# Main_PDSplitter.net
KiCad netlist of a schematic drawn in Altium Designer
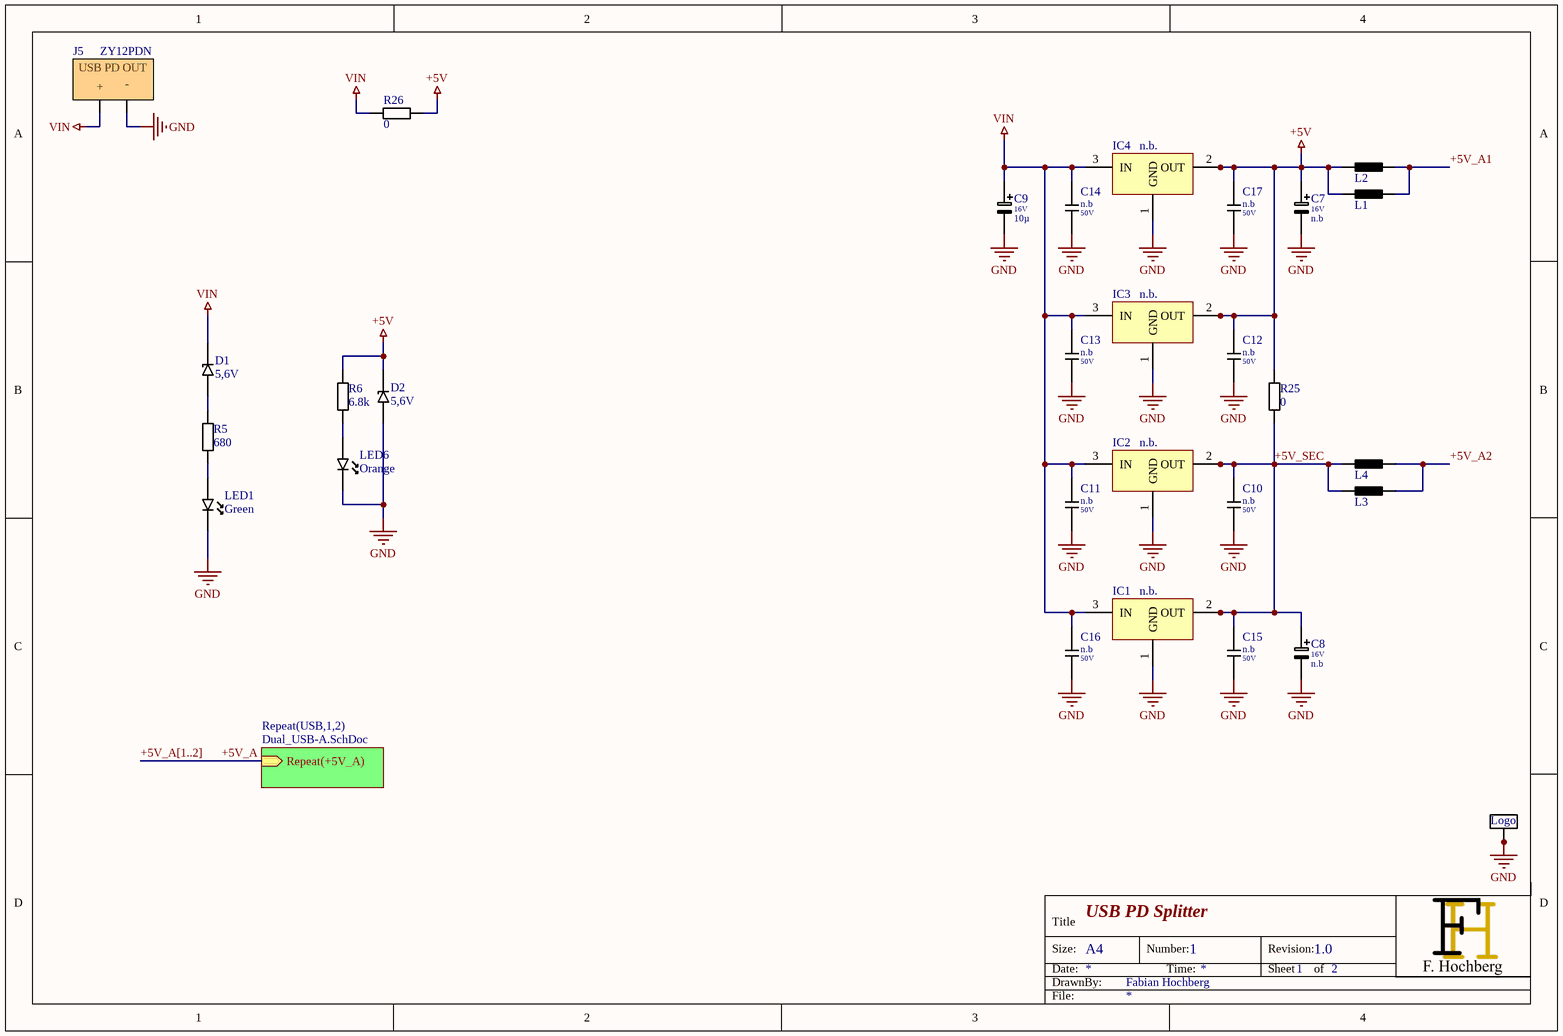
[diagram p0: Main_PDSplitter.SchDoc]

(export (version "E")
  (design (tool "Eeschema 10.0.6"))
  (components
    (comp (ref "C7")
      (value "n.b")
      (footprint "CAPAE_4x5.4")
      (description "Elko")
      (fields (field (name "VOLTAGE") "16V") (field (name "Comment") "n.b."))
      (libsource (lib "Passives_FH") (part "C POL"))
    )
    (comp (ref "C8")
      (value "n.b")
      (footprint "CAPAE_4x5.4")
      (description "Elko")
      (fields (field (name "VOLTAGE") "16V") (field (name "Comment") "n.b."))
      (libsource (lib "Passives_FH") (part "C POL"))
    )
    (comp (ref "C9")
      (value "10µ")
      (footprint "CAPAE_4x5.4")
      (description "Elko")
      (fields (field (name "VOLTAGE") "16V") (field (name "Comment") "10µ_16V"))
      (libsource (lib "Passives_FH") (part "C POL"))
    )
    (comp (ref "C10")
      (value "n.b")
      (footprint "0603_C")
      (description "Keramikkondensator")
      (fields (field (name "VOLTAGE") "50V") (field (name "Comment") "n.b."))
      (libsource (lib "Passives_FH") (part "C"))
    )
    (comp (ref "C11")
      (value "n.b")
      (footprint "0603_C")
      (description "Keramikkondensator")
      (fields (field (name "VOLTAGE") "50V") (field (name "Comment") "n.b."))
      (libsource (lib "Passives_FH") (part "C"))
    )
    (comp (ref "C12")
      (value "n.b")
      (footprint "0603_C")
      (description "Keramikkondensator")
      (fields (field (name "VOLTAGE") "50V") (field (name "Comment") "n.b."))
      (libsource (lib "Passives_FH") (part "C"))
    )
    (comp (ref "C13")
      (value "n.b")
      (footprint "0603_C")
      (description "Keramikkondensator")
      (fields (field (name "VOLTAGE") "50V") (field (name "Comment") "n.b."))
      (libsource (lib "Passives_FH") (part "C"))
    )
    (comp (ref "C14")
      (value "n.b")
      (footprint "0603_C")
      (description "Keramikkondensator")
      (fields (field (name "VOLTAGE") "50V") (field (name "Comment") "n.b."))
      (libsource (lib "Passives_FH") (part "C"))
    )
    (comp (ref "C15")
      (value "n.b")
      (footprint "0603_C")
      (description "Keramikkondensator")
      (fields (field (name "VOLTAGE") "50V") (field (name "Comment") "n.b."))
      (libsource (lib "Passives_FH") (part "C"))
    )
    (comp (ref "C16")
      (value "n.b")
      (footprint "0603_C")
      (description "Keramikkondensator")
      (fields (field (name "VOLTAGE") "50V") (field (name "Comment") "n.b."))
      (libsource (lib "Passives_FH") (part "C"))
    )
    (comp (ref "C17")
      (value "n.b")
      (footprint "0603_C")
      (description "Keramikkondensator")
      (fields (field (name "VOLTAGE") "50V") (field (name "Comment") "n.b."))
      (libsource (lib "Passives_FH") (part "C"))
    )
    (comp (ref "D1")
      (value "5,6V")
      (footprint "MINIMELF-SOD80")
      (description "Zener Diode")
      (libsource (lib "Semiconductors_FH") (part "Zener Diode"))
    )
    (comp (ref "D2")
      (value "5,6V")
      (footprint "MINIMELF-SOD80")
      (description "Zener Diode")
      (libsource (lib "Semiconductors_FH") (part "Zener Diode"))
    )
    (comp (ref "IC1")
      (value "n.b.")
      (footprint "SOT223")
      (description "Fixedvoltage LDO, Pinassignment A")
      (fields (field (name "VOLTAGE") "5V"))
      (libsource (lib "ICs_Supply_FH") (part "LD1117AG"))
    )
    (comp (ref "IC2")
      (value "n.b.")
      (footprint "SOT223")
      (description "Fixedvoltage LDO, Pinassignment A")
      (fields (field (name "VOLTAGE") "5V"))
      (libsource (lib "ICs_Supply_FH") (part "LD1117AG"))
    )
    (comp (ref "IC3")
      (value "n.b.")
      (footprint "SOT223")
      (description "Fixedvoltage LDO, Pinassignment A")
      (fields (field (name "VOLTAGE") "5V"))
      (libsource (lib "ICs_Supply_FH") (part "LD1117AG"))
    )
    (comp (ref "IC4")
      (value "n.b.")
      (footprint "SOT223")
      (description "Fixedvoltage LDO, Pinassignment A")
      (fields (field (name "VOLTAGE") "5V"))
      (libsource (lib "ICs_Supply_FH") (part "LD1117AG"))
    )
    (comp (ref "J5")
      (value "ZY12PDN")
      (footprint "ZY12PDN_BRPCB")
      (libsource (lib "Miscellaneous_FH") (part "ZY12PDN"))
    )
    (comp (ref "L1")
      (value "100 Ohm @ 100MHz")
      (footprint "0603_L")
      (description "0,15 Ohm 1A max\r\n100 Ohm @ 100MHz")
      (libsource (lib "Passives_FH") (part "L"))
    )
    (comp (ref "L2")
      (value "100 Ohm @ 100MHz")
      (footprint "0603_L")
      (description "0,15 Ohm 1A max\r\n100 Ohm @ 100MHz")
      (libsource (lib "Passives_FH") (part "L"))
    )
    (comp (ref "L3")
      (value "100 Ohm @ 100MHz")
      (footprint "0603_L")
      (description "0,15 Ohm 1A max\r\n100 Ohm @ 100MHz")
      (libsource (lib "Passives_FH") (part "L"))
    )
    (comp (ref "L4")
      (value "100 Ohm @ 100MHz")
      (footprint "0603_L")
      (description "0,15 Ohm 1A max\r\n100 Ohm @ 100MHz")
      (libsource (lib "Passives_FH") (part "L"))
    )
    (comp (ref "LED1")
      (value "Green")
      (footprint "0603_LED")
      (description "LED")
      (fields (field (name "COLOR") "Green"))
      (libsource (lib "Optical_FH") (part "LED"))
    )
    (comp (ref "LED6")
      (value "Orange")
      (footprint "0603_LED")
      (description "LED")
      (fields (field (name "COLOR") "Orange"))
      (libsource (lib "Optical_FH") (part "LED"))
    )
    (comp (ref "Logo_FH1")
      (value "Logo")
      (footprint "Logo FH")
      (description "8x8 mm Logo Fabian Hochberg")
      (libsource (lib "PCB_Stickers") (part "Logo"))
    )
    (comp (ref "R5")
      (value "680")
      (footprint "0603_R")
      (description "R")
      (libsource (lib "Passives_FH") (part "R"))
    )
    (comp (ref "R6")
      (value "6.8k")
      (footprint "0603_R")
      (description "R")
      (libsource (lib "Passives_FH") (part "R"))
    )
    (comp (ref "R25") (value "0") (footprint "0603_R") (description "R") (libsource (lib "") (part "R_2")))
    (comp (ref "R26") (value "0") (footprint "0603_R") (description "R") (libsource (lib "") (part "R_1")))
  )
  (nets
    (net (code "1") (name "+5V") (class "Default")
      (node (ref "C12") (pin "1") (pinfunction "1_1") (pintype "passive"))
      (node (ref "C17") (pin "1") (pinfunction "1_1") (pintype "passive"))
      (node (ref "C7") (pin "1") (pinfunction "1_1") (pintype "passive"))
      (node (ref "D2") (pin "2") (pinfunction "K_2") (pintype "passive"))
      (node (ref "IC3") (pin "2") (pinfunction "OUT_2") (pintype "power_in"))
      (node (ref "IC3") (pin "4") (pinfunction "OUT_4") (pintype "power_in"))
      (node (ref "IC4") (pin "2") (pinfunction "OUT_2") (pintype "power_in"))
      (node (ref "IC4") (pin "4") (pinfunction "OUT_4") (pintype "power_in"))
      (node (ref "L1") (pin "1") (pinfunction "1_1") (pintype "passive"))
      (node (ref "L2") (pin "1") (pinfunction "1_1") (pintype "passive"))
      (node (ref "R25") (pin "1") (pinfunction "1_1") (pintype "passive"))
      (node (ref "R26") (pin "1") (pinfunction "1_1") (pintype "passive"))
      (node (ref "R6") (pin "2") (pinfunction "2_2") (pintype "passive"))
    )
    (net (code "3") (name "/+5V_A1") (class "Default")
      (node (ref "L1") (pin "2") (pinfunction "2_2") (pintype "passive"))
      (node (ref "L2") (pin "2") (pinfunction "2_2") (pintype "passive"))
    )
    (net (code "4") (name "/+5V_A2") (class "Default")
      (node (ref "L3") (pin "2") (pinfunction "2_2") (pintype "passive"))
      (node (ref "L4") (pin "2") (pinfunction "2_2") (pintype "passive"))
    )
    (net (code "6") (name "/+5V_SEC") (class "Default")
      (node (ref "C10") (pin "1") (pinfunction "1_1") (pintype "passive"))
      (node (ref "C15") (pin "1") (pinfunction "1_1") (pintype "passive"))
      (node (ref "C8") (pin "1") (pinfunction "1_1") (pintype "passive"))
      (node (ref "IC1") (pin "2") (pinfunction "OUT_2") (pintype "power_in"))
      (node (ref "IC1") (pin "4") (pinfunction "OUT_4") (pintype "power_in"))
      (node (ref "IC2") (pin "2") (pinfunction "OUT_2") (pintype "power_in"))
      (node (ref "IC2") (pin "4") (pinfunction "OUT_4") (pintype "power_in"))
      (node (ref "L3") (pin "1") (pinfunction "1_1") (pintype "passive"))
      (node (ref "L4") (pin "1") (pinfunction "1_1") (pintype "passive"))
      (node (ref "R25") (pin "2") (pinfunction "2_2") (pintype "passive"))
    )
    (net (code "7") (name "GND") (class "Default")
      (node (ref "C10") (pin "2") (pinfunction "2_2") (pintype "passive"))
      (node (ref "C11") (pin "2") (pinfunction "2_2") (pintype "passive"))
      (node (ref "C12") (pin "2") (pinfunction "2_2") (pintype "passive"))
      (node (ref "C13") (pin "2") (pinfunction "2_2") (pintype "passive"))
      (node (ref "C14") (pin "2") (pinfunction "2_2") (pintype "passive"))
      (node (ref "C15") (pin "2") (pinfunction "2_2") (pintype "passive"))
      (node (ref "C16") (pin "2") (pinfunction "2_2") (pintype "passive"))
      (node (ref "C17") (pin "2") (pinfunction "2_2") (pintype "passive"))
      (node (ref "C7") (pin "2") (pinfunction "2_2") (pintype "passive"))
      (node (ref "C8") (pin "2") (pinfunction "2_2") (pintype "passive"))
      (node (ref "C9") (pin "2") (pinfunction "2_2") (pintype "passive"))
      (node (ref "D2") (pin "1") (pinfunction "A_1") (pintype "passive"))
      (node (ref "IC1") (pin "1") (pinfunction "GND_1") (pintype "passive"))
      (node (ref "IC2") (pin "1") (pinfunction "GND_1") (pintype "passive"))
      (node (ref "IC3") (pin "1") (pinfunction "GND_1") (pintype "passive"))
      (node (ref "IC4") (pin "1") (pinfunction "GND_1") (pintype "passive"))
      (node (ref "J5") (pin "2") (pinfunction "-_2") (pintype "power_in"))
      (node (ref "LED1") (pin "1") (pinfunction "K_1") (pintype "passive"))
      (node (ref "LED6") (pin "1") (pinfunction "K_1") (pintype "passive"))
      (node (ref "Logo_FH1") (pin "1") (pinfunction "0_1") (pintype "passive"))
      (node (ref "Logo_FH1") (pin "2") (pinfunction "1_2") (pintype "passive"))
      (node (ref "Logo_FH1") (pin "3") (pinfunction "2_3") (pintype "passive"))
      (node (ref "Logo_FH1") (pin "4") (pinfunction "3_4") (pintype "passive"))
    )
    (net (code "8") (name "Net-(D1-A)") (class "Default")
      (node (ref "D1") (pin "1") (pinfunction "A_1") (pintype "passive"))
      (node (ref "R5") (pin "2") (pinfunction "2_2") (pintype "passive"))
    )
    (net (code "9") (name "Net-(LED1-A)") (class "Default")
      (node (ref "LED1") (pin "2") (pinfunction "A_2") (pintype "passive"))
      (node (ref "R5") (pin "1") (pinfunction "1_1") (pintype "passive"))
    )
    (net (code "10") (name "Net-(LED6-A)") (class "Default")
      (node (ref "LED6") (pin "2") (pinfunction "A_2") (pintype "passive"))
      (node (ref "R6") (pin "1") (pinfunction "1_1") (pintype "passive"))
    )
    (net (code "11") (name "VIN") (class "Default")
      (node (ref "C11") (pin "1") (pinfunction "1_1") (pintype "passive"))
      (node (ref "C13") (pin "1") (pinfunction "1_1") (pintype "passive"))
      (node (ref "C14") (pin "1") (pinfunction "1_1") (pintype "passive"))
      (node (ref "C16") (pin "1") (pinfunction "1_1") (pintype "passive"))
      (node (ref "C9") (pin "1") (pinfunction "1_1") (pintype "passive"))
      (node (ref "D1") (pin "2") (pinfunction "K_2") (pintype "passive"))
      (node (ref "IC1") (pin "3") (pinfunction "IN_3") (pintype "passive"))
      (node (ref "IC2") (pin "3") (pinfunction "IN_3") (pintype "passive"))
      (node (ref "IC3") (pin "3") (pinfunction "IN_3") (pintype "passive"))
      (node (ref "IC4") (pin "3") (pinfunction "IN_3") (pintype "passive"))
      (node (ref "J5") (pin "1") (pinfunction "+_1") (pintype "power_in"))
      (node (ref "R26") (pin "2") (pinfunction "2_2") (pintype "passive"))
    )
  )
)
